# HV_Fuses.net
KiCad netlist of a schematic drawn in Altium Designer
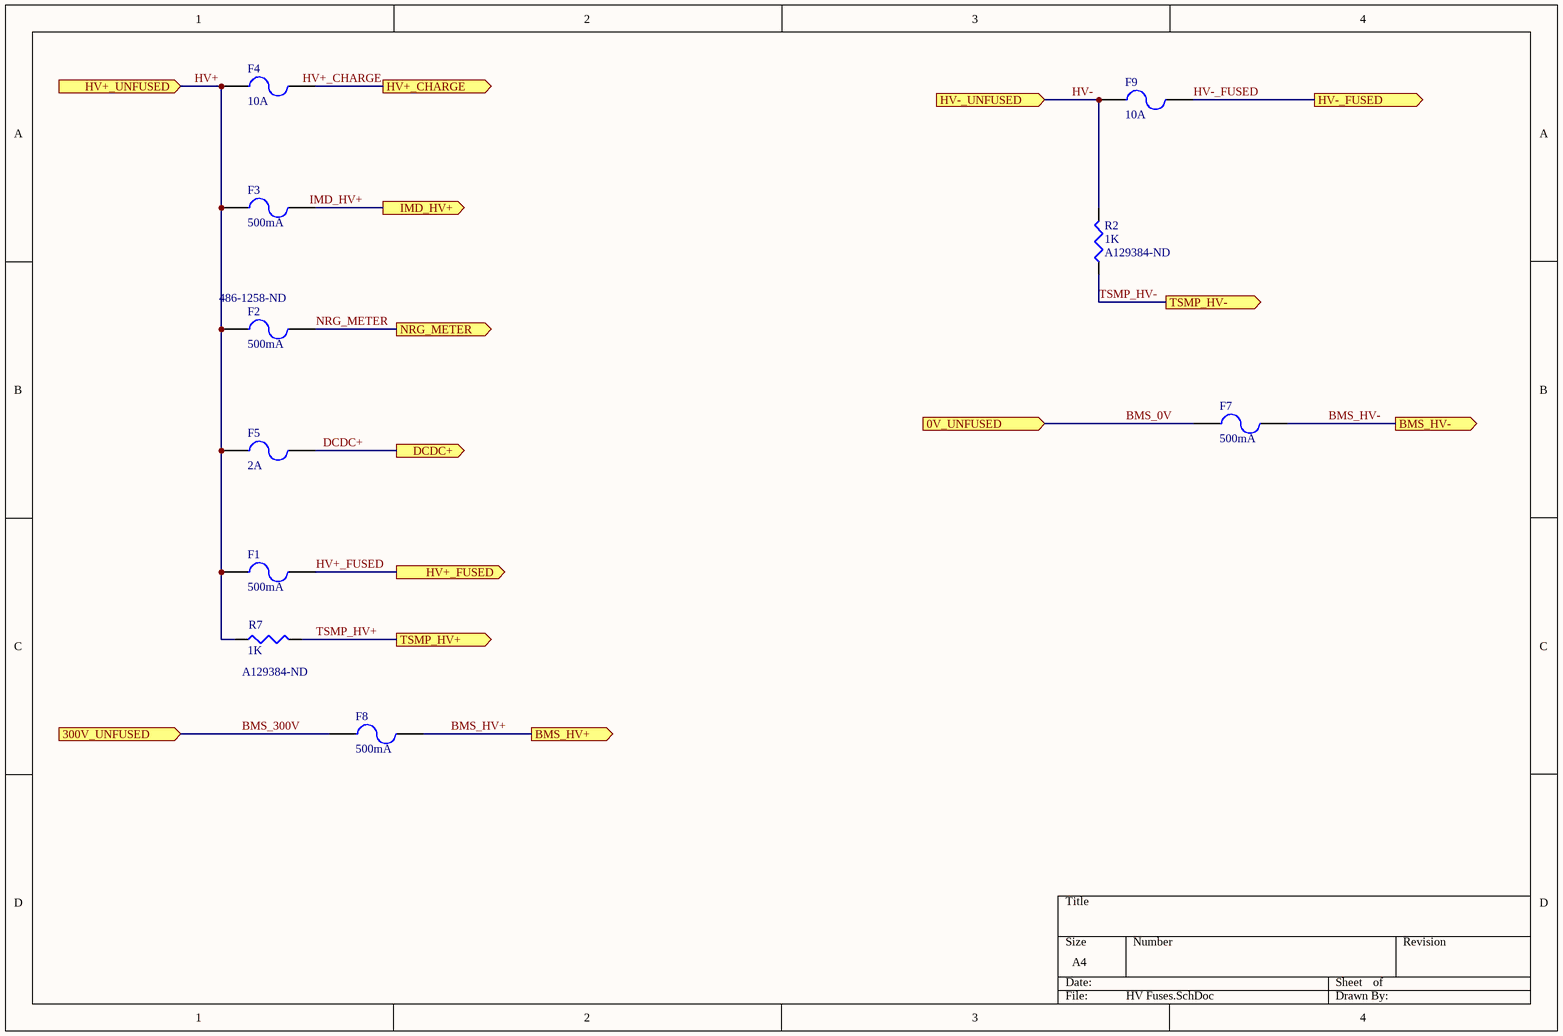
[diagram p0: HV Fuses.SchDoc]

(export (version "E")
  (design (tool "Eeschema 10.0.6"))
  (components
    (comp (ref "F1")
      (value "500mA")
      (footprint "FUSEHOLDER 5X20")
      (description "0031.8201: FUSE BLOK CARTRIDGE 500V 10A PCB")
      (fields (field (name "PUBLISHER") "Altium Limited"))
      (libsource (lib "Miscellaneous Devices") (part "Fuse 2"))
    )
    (comp (ref "F2")
      (value "500mA")
      (footprint "FUSEHOLDER 5X20")
      (description "0031.8201: FUSE BLOK CARTRIDGE 500V 10A PCB")
      (fields
        (field (name "SUPPLIER PART NUMBER 1") "486-1258-ND")
        (field (name "PUBLISHER") "Altium Limited")
      )
      (libsource (lib "Miscellaneous Devices") (part "Fuse 2"))
    )
    (comp (ref "F3")
      (value "500mA")
      (footprint "FUSEHOLDER 5X20")
      (description "0031.8201: FUSE BLOK CARTRIDGE 500V 10A PCB")
      (fields (field (name "PUBLISHER") "Altium Limited"))
      (libsource (lib "Miscellaneous Devices") (part "Fuse 2"))
    )
    (comp (ref "F4")
      (value "10A")
      (footprint "FUSEHOLDER 5X20")
      (description "0031.8201: FUSE BLOK CARTRIDGE 500V 10A PCB")
      (fields (field (name "PUBLISHER") "Altium Limited"))
      (libsource (lib "altium-import") (part "root_2_Fuse 2_"))
    )
    (comp (ref "F5")
      (value "2A")
      (footprint "FUSEHOLDER 5X20")
      (description "0031.8201: FUSE BLOK CARTRIDGE 500V 10A PCB")
      (fields (field (name "PUBLISHER") "Altium Limited"))
      (libsource (lib "Miscellaneous Devices") (part "Fuse 2"))
    )
    (comp (ref "F7")
      (value "500mA")
      (footprint "FUSEHOLDER 5X20")
      (description "0031.8201: FUSE BLOK CARTRIDGE 500V 10A PCB")
      (fields (field (name "PUBLISHER") "Altium Limited"))
      (libsource (lib "Miscellaneous Devices") (part "Fuse 2"))
    )
    (comp (ref "F8")
      (value "500mA")
      (footprint "FUSEHOLDER 5X20")
      (description "0031.8201: FUSE BLOK CARTRIDGE 500V 10A PCB")
      (fields (field (name "PUBLISHER") "Altium Limited"))
      (libsource (lib "Miscellaneous Devices") (part "Fuse 2"))
    )
    (comp (ref "F9")
      (value "10A")
      (footprint "FUSEHOLDER 5X20")
      (description "0031.8201: FUSE BLOK CARTRIDGE 500V 10A PCB")
      (fields (field (name "PUBLISHER") "Altium Limited"))
      (libsource (lib "Miscellaneous Devices") (part "Fuse 2"))
    )
    (comp (ref "R2")
      (value "1K")
      (footprint "AXIAL RESISTOR WW 14W")
      (description "20J1K0E: RES 1K OHM 10W 5% AXIAL")
      (fields
        (field (name "SUPPLIER PART NUMBER 1") "A129384-ND")
        (field (name "PUBLISHER") "Altium Limited")
      )
      (libsource (lib "Miscellaneous Devices") (part "Res3"))
    )
    (comp (ref "R7")
      (value "1K")
      (footprint "AXIAL RESISTOR WW 14W")
      (description "20J1K0E: RES 1K OHM 10W 5% AXIAL")
      (fields
        (field (name "SUPPLIER PART NUMBER 1") "A129384-ND")
        (field (name "PUBLISHER") "Altium Limited")
      )
      (libsource (lib "Miscellaneous Devices") (part "Res3"))
    )
  )
  (nets
    (net (code "1") (name "/BMS_0V") (class "Default")
      (node (ref "F7") (pin "2") (pinfunction "2_2") (pintype "passive"))
    )
    (net (code "2") (name "/BMS_300V") (class "Default")
      (node (ref "F8") (pin "2") (pinfunction "2_2") (pintype "passive"))
    )
    (net (code "3") (name "/BMS_HV+") (class "Default")
      (node (ref "F8") (pin "1") (pinfunction "1_1") (pintype "passive"))
    )
    (net (code "4") (name "/BMS_HV-") (class "Default")
      (node (ref "F7") (pin "1") (pinfunction "1_1") (pintype "passive"))
    )
    (net (code "5") (name "/DCDC+") (class "Default")
      (node (ref "F5") (pin "1") (pinfunction "1_1") (pintype "passive"))
    )
    (net (code "6") (name "/HV+") (class "Default")
      (node (ref "F1") (pin "2") (pinfunction "2_2") (pintype "passive"))
      (node (ref "F2") (pin "2") (pinfunction "2_2") (pintype "passive"))
      (node (ref "F3") (pin "2") (pinfunction "2_2") (pintype "passive"))
      (node (ref "F4") (pin "2") (pinfunction "2_2") (pintype "passive"))
      (node (ref "F5") (pin "2") (pinfunction "2_2") (pintype "passive"))
      (node (ref "R7") (pin "1") (pinfunction "1_1") (pintype "passive"))
    )
    (net (code "7") (name "/HV+_CHARGE") (class "Default")
      (node (ref "F4") (pin "1") (pinfunction "1_1") (pintype "passive"))
    )
    (net (code "8") (name "/HV+_FUSED") (class "Default")
      (node (ref "F1") (pin "1") (pinfunction "1_1") (pintype "passive"))
    )
    (net (code "9") (name "/HV-") (class "Default")
      (node (ref "F9") (pin "2") (pinfunction "2_2") (pintype "passive"))
      (node (ref "R2") (pin "2") (pinfunction "2_2") (pintype "passive"))
    )
    (net (code "10") (name "/HV-_FUSED") (class "Default")
      (node (ref "F9") (pin "1") (pinfunction "1_1") (pintype "passive"))
    )
    (net (code "11") (name "/IMD_HV+") (class "Default")
      (node (ref "F3") (pin "1") (pinfunction "1_1") (pintype "passive"))
    )
    (net (code "12") (name "/NRG_METER") (class "Default")
      (node (ref "F2") (pin "1") (pinfunction "1_1") (pintype "passive"))
    )
    (net (code "13") (name "/TSMP_HV+") (class "Default")
      (node (ref "R7") (pin "2") (pinfunction "2_2") (pintype "passive"))
    )
    (net (code "14") (name "/TSMP_HV-") (class "Default")
      (node (ref "R2") (pin "1") (pinfunction "1_1") (pintype "passive"))
    )
  )
)
